# X10-Isolation.net
KiCad netlist of a schematic drawn in Altium Designer
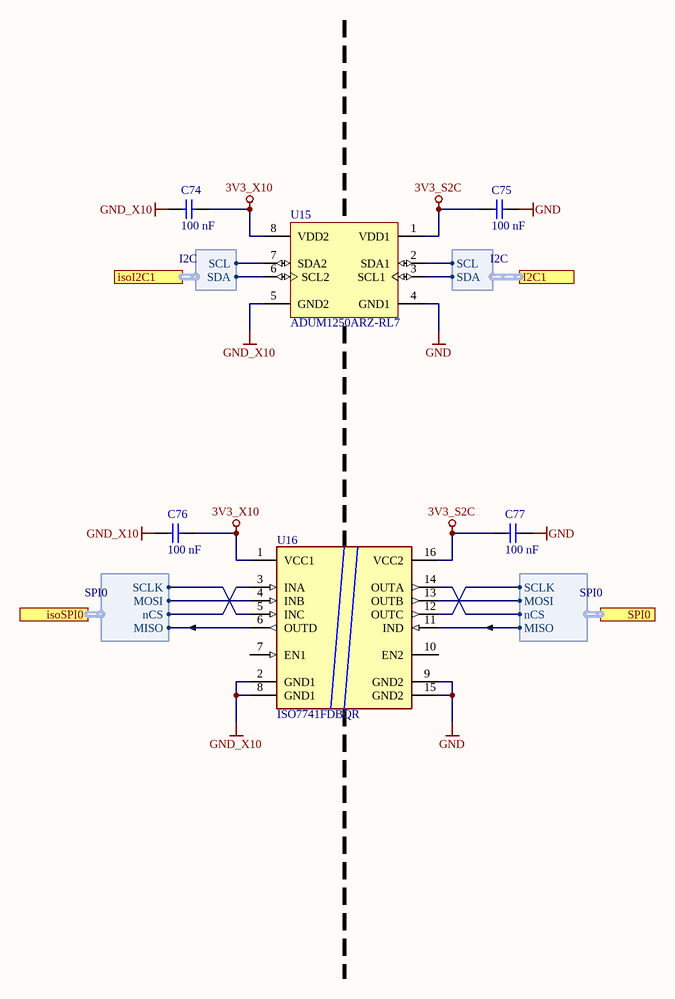
[diagram p0: X10-Isolation.SchDoc]

(export (version "E")
  (design (tool "Eeschema 10.0.6"))
  (components
    (comp (ref "C74")
      (value "100 nF")
      (footprint "C_0603_TE")
      (description "Generic capacitor")
      (fields
        (field (name "MANUFACTURER PART NUMBER") "UZgen_C_0603_100nF_50V_X7R")
        (field (name "MANUFACTURER") "UZgen")
        (field (name "CREATED FROM") "AGeiger")
      )
      (libsource (lib "user") (part "CAP-NP"))
    )
    (comp (ref "C75")
      (value "100 nF")
      (footprint "C_0603_TE")
      (description "Generic capacitor")
      (fields
        (field (name "MANUFACTURER PART NUMBER") "UZgen_C_0603_100nF_50V_X7R")
        (field (name "MANUFACTURER") "UZgen")
        (field (name "CREATED FROM") "AGeiger")
      )
      (libsource (lib "user") (part "CAP-NP"))
    )
    (comp (ref "C76")
      (value "100 nF")
      (footprint "C_0603_TE")
      (description "Generic capacitor")
      (fields
        (field (name "MANUFACTURER PART NUMBER") "UZgen_C_0603_100nF_50V_X7R")
        (field (name "MANUFACTURER") "UZgen")
        (field (name "CREATED FROM") "AGeiger")
      )
      (libsource (lib "user") (part "CAP-NP"))
    )
    (comp (ref "C77")
      (value "100 nF")
      (footprint "C_0603_TE")
      (description "Generic capacitor")
      (fields
        (field (name "MANUFACTURER PART NUMBER") "UZgen_C_0603_100nF_50V_X7R")
        (field (name "MANUFACTURER") "UZgen")
        (field (name "CREATED FROM") "AGeiger")
      )
      (libsource (lib "user") (part "CAP-NP"))
    )
    (comp (ref "U15")
      (value "ADUM1250ARZ-RL7")
      (footprint "ADI-R-8_N")
      (description "Digital Isolators DUAL-Hot-Swappable 12C Isolators")
      (fields
        (field (name "MANUFACTURER") "Analog Devices Inc.")
        (field (name "LCSC PART NUMBER") "C13839")
        (field (name "CREATED FROM") "FRosner")
      )
      (libsource (lib "user") (part "ADUM1250"))
    )
    (comp (ref "U16")
      (value "ISO7741FDBQR")
      (footprint "SOP64P600X175-16N")
      (description "ISO774xT-Q1 High-Speed, Reinforced Quad-Channel Digital Isolators With Integrated")
      (fields
        (field (name "MANUFACTURER") "Texas Instruments")
        (field (name "LCSC PART NUMBER") "C2872241")
        (field (name "CREATED FROM") "FRosner")
      )
      (libsource (lib "user") (part "ISO7741"))
    )
  )
  (nets
    (net (code "5") (name "3V3_S2C") (class "Default")
      (node (ref "C75") (pin "2") (pinfunction "2_2") (pintype "passive"))
      (node (ref "C77") (pin "2") (pinfunction "2_2") (pintype "passive"))
      (node (ref "U15") (pin "1") (pinfunction "VDD1_1") (pintype "power_in"))
      (node (ref "U16") (pin "16") (pinfunction "VCC2_16") (pintype "passive"))
    )
    (net (code "6") (name "3V3_X10") (class "Default")
      (node (ref "C74") (pin "1") (pinfunction "1_1") (pintype "passive"))
      (node (ref "C76") (pin "1") (pinfunction "1_1") (pintype "passive"))
      (node (ref "U15") (pin "8") (pinfunction "VDD2_8") (pintype "power_in"))
      (node (ref "U16") (pin "1") (pinfunction "VCC1_1") (pintype "passive"))
    )
    (net (code "7") (name "GND") (class "Default")
      (node (ref "C75") (pin "1") (pinfunction "1_1") (pintype "passive"))
      (node (ref "C77") (pin "1") (pinfunction "1_1") (pintype "passive"))
      (node (ref "U15") (pin "4") (pinfunction "GND1_4") (pintype "power_in"))
      (node (ref "U16") (pin "15") (pinfunction "GND2_15") (pintype "passive"))
      (node (ref "U16") (pin "9") (pinfunction "GND2_9") (pintype "passive"))
    )
    (net (code "8") (name "GND_X10") (class "Default")
      (node (ref "C74") (pin "2") (pinfunction "2_2") (pintype "passive"))
      (node (ref "C76") (pin "2") (pinfunction "2_2") (pintype "passive"))
      (node (ref "U15") (pin "5") (pinfunction "GND2_5") (pintype "power_in"))
      (node (ref "U16") (pin "2") (pinfunction "GND1_2") (pintype "passive"))
      (node (ref "U16") (pin "8") (pinfunction "GND1_8") (pintype "passive"))
    )
    (net (code "9") (name "unconnected-(U15-SCL1-Pad3)") (class "Default")
      (node (ref "U15") (pin "3") (pinfunction "SCL1_3") (pintype "bidirectional"))
    )
    (net (code "10") (name "unconnected-(U15-SCL2-Pad6)") (class "Default")
      (node (ref "U15") (pin "6") (pinfunction "SCL2_6") (pintype "bidirectional"))
    )
    (net (code "11") (name "unconnected-(U15-SDA1-Pad2)") (class "Default")
      (node (ref "U15") (pin "2") (pinfunction "SDA1_2") (pintype "bidirectional"))
    )
    (net (code "12") (name "unconnected-(U15-SDA2-Pad7)") (class "Default")
      (node (ref "U15") (pin "7") (pinfunction "SDA2_7") (pintype "bidirectional"))
    )
    (net (code "13") (name "unconnected-(U16-EN1-Pad7)") (class "Default")
      (node (ref "U16") (pin "7") (pinfunction "EN1_7") (pintype "input"))
    )
    (net (code "14") (name "unconnected-(U16-EN2-Pad10)") (class "Default")
      (node (ref "U16") (pin "10") (pinfunction "EN2_10") (pintype "passive"))
    )
    (net (code "15") (name "unconnected-(U16-INA-Pad3)") (class "Default")
      (node (ref "U16") (pin "3") (pinfunction "INA_3") (pintype "input"))
    )
    (net (code "16") (name "unconnected-(U16-INB-Pad4)") (class "Default")
      (node (ref "U16") (pin "4") (pinfunction "INB_4") (pintype "input"))
    )
    (net (code "17") (name "unconnected-(U16-INC-Pad5)") (class "Default")
      (node (ref "U16") (pin "5") (pinfunction "INC_5") (pintype "input"))
    )
    (net (code "18") (name "unconnected-(U16-IND-Pad11)") (class "Default")
      (node (ref "U16") (pin "11") (pinfunction "IND_11") (pintype "input"))
    )
    (net (code "19") (name "unconnected-(U16-OUTA-Pad14)") (class "Default")
      (node (ref "U16") (pin "14") (pinfunction "OUTA_14") (pintype "output"))
    )
    (net (code "20") (name "unconnected-(U16-OUTB-Pad13)") (class "Default")
      (node (ref "U16") (pin "13") (pinfunction "OUTB_13") (pintype "output"))
    )
    (net (code "21") (name "unconnected-(U16-OUTC-Pad12)") (class "Default")
      (node (ref "U16") (pin "12") (pinfunction "OUTC_12") (pintype "output"))
    )
    (net (code "22") (name "unconnected-(U16-OUTD-Pad6)") (class "Default")
      (node (ref "U16") (pin "6") (pinfunction "OUTD_6") (pintype "output"))
    )
  )
)
